# Microcontroller.net
KiCad netlist of a schematic drawn in Altium Designer
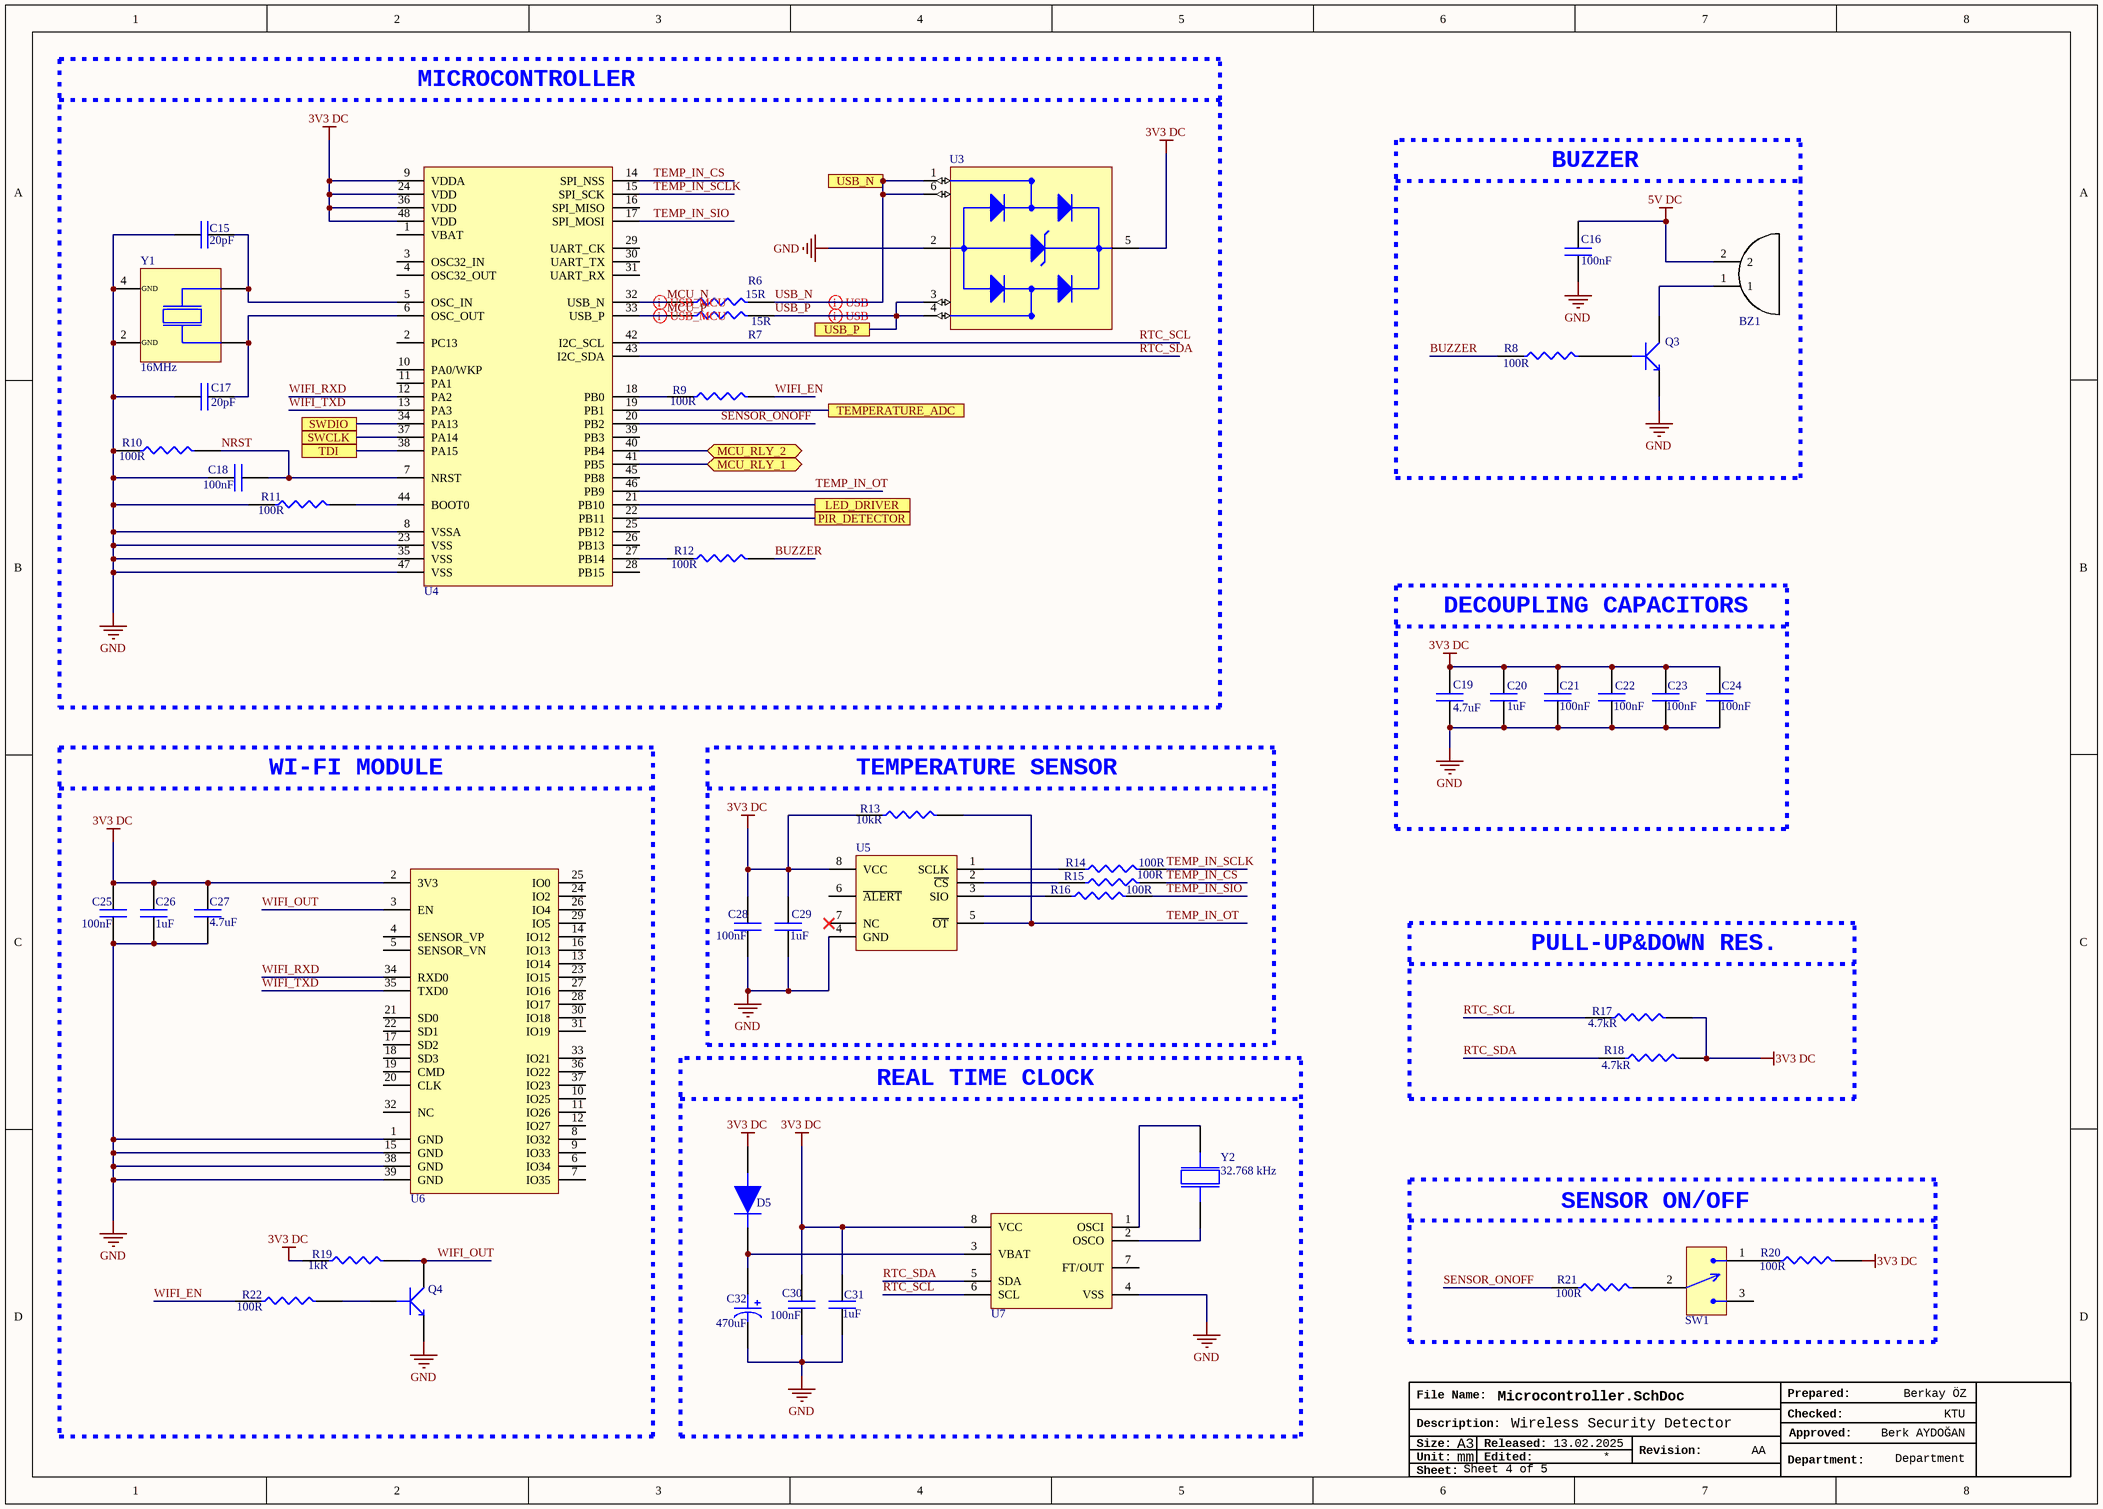
[diagram p0: Microcontroller.SchDoc]

(export (version "E")
  (design (tool "Eeschema 10.0.6"))
  (components
    (comp (ref "BZ1")
      (value "CMI-9605IC-0580T")
      (footprint "CMI-9605IC")
      (description "Buzzers Indicator, Internally Driven Magnetic 5 V 30mA 2.7kHz 80dB @ 5V, 10cm Through Hole PC Pins")
      (fields (field (name "MANUFACTURER") "CUI Devices") (field (name "DESIGNED BY") "berkay"))
      (libsource (lib "FirstProject_Library") (part "CMI-9605IC-0580T"))
    )
    (comp (ref "C15")
      (value "CL10C200JB8NNNC")
      (footprint "CAP_0603")
      (description "Ceramic Capacitor, 20pF, 50 V, 5%, Pad SMD 0603 [1608 Metric]")
      (fields
        (field (name "MANUFACTURER") "Samsung")
        (field (name "CAPACITANCE") "20pF")
        (field (name "DESIGNED BY") "berkay")
      )
      (libsource (lib "FirstProject_Library") (part "CAP CER 20pF 0603"))
    )
    (comp (ref "C16")
      (value "CL21B104KBCNNNC")
      (footprint "CAP_0805")
      (description "Ceramic Capacitor, 0.1 uF, 50 V, ï¿½ 10%, X7R, 0805 [2012 Metric]")
      (fields
        (field (name "MANUFACTURER") "Samsung")
        (field (name "TOLERANCE") "10%")
        (field (name "CAPACITANCE") "100nF")
        (field (name "DESIGNED BY") "berkay")
      )
      (libsource (lib "FirstProject_Library") (part "CAP CER 100nF 0805"))
    )
    (comp (ref "C17")
      (value "CL10C200JB8NNNC")
      (footprint "CAP_0603")
      (description "Ceramic Capacitor, 20pF, 50 V, 5%, Pad SMD 0603 [1608 Metric]")
      (fields
        (field (name "MANUFACTURER") "Samsung")
        (field (name "CAPACITANCE") "20pF")
        (field (name "DESIGNED BY") "berkay")
      )
      (libsource (lib "FirstProject_Library") (part "CAP CER 20pF 0603"))
    )
    (comp (ref "C18")
      (value "CL21B104KBCNNNC")
      (footprint "CAP_0805")
      (description "Ceramic Capacitor, 0.1 uF, 50 V, ï¿½ 10%, X7R, 0805 [2012 Metric]")
      (fields
        (field (name "MANUFACTURER") "Samsung")
        (field (name "TOLERANCE") "10%")
        (field (name "CAPACITANCE") "100nF")
        (field (name "DESIGNED BY") "berkay")
      )
      (libsource (lib "FirstProject_Library") (part "CAP CER 100nF 0805"))
    )
    (comp (ref "C19")
      (value "CL21A475KAQNNNE")
      (footprint "CAP_0805")
      (description "Ceramic Capacitor, 4.7 uF, 25 V, ± 10%, X5R, 0805 [2012 Metric]")
      (fields
        (field (name "MANUFACTURER") "Samsung")
        (field (name "TOLERANCE") "10%")
        (field (name "CAPACITANCE") "4.7uF")
        (field (name "DESIGNED BY") "berkay")
      )
      (libsource (lib "FirstProject_Library") (part "CAP CER 4.7uF 0805"))
    )
    (comp (ref "C20")
      (value "CL21B105KBFNNNE")
      (footprint "CAP_0805")
      (description "Ceramic Capacitor, 1 uF, 50 V, ï¿½ 10%, X7R, 0805 [2012 Metric]")
      (fields
        (field (name "MANUFACTURER") "Samsung")
        (field (name "TOLERANCE") "10%")
        (field (name "CAPACITANCE") "1uF")
        (field (name "DESIGNED BY") "berkay")
      )
      (libsource (lib "FirstProject_Library") (part "CAP CER 1uF 0805"))
    )
    (comp (ref "C21")
      (value "CL21B104KBCNNNC")
      (footprint "CAP_0805")
      (description "Ceramic Capacitor, 0.1 uF, 50 V, ï¿½ 10%, X7R, 0805 [2012 Metric]")
      (fields
        (field (name "MANUFACTURER") "Samsung")
        (field (name "TOLERANCE") "10%")
        (field (name "CAPACITANCE") "100nF")
        (field (name "DESIGNED BY") "berkay")
      )
      (libsource (lib "FirstProject_Library") (part "CAP CER 100nF 0805"))
    )
    (comp (ref "C22")
      (value "CL21B104KBCNNNC")
      (footprint "CAP_0805")
      (description "Ceramic Capacitor, 0.1 uF, 50 V, ï¿½ 10%, X7R, 0805 [2012 Metric]")
      (fields
        (field (name "MANUFACTURER") "Samsung")
        (field (name "TOLERANCE") "10%")
        (field (name "CAPACITANCE") "100nF")
        (field (name "DESIGNED BY") "berkay")
      )
      (libsource (lib "FirstProject_Library") (part "CAP CER 100nF 0805"))
    )
    (comp (ref "C23")
      (value "CL21B104KBCNNNC")
      (footprint "CAP_0805")
      (description "Ceramic Capacitor, 0.1 uF, 50 V, ï¿½ 10%, X7R, 0805 [2012 Metric]")
      (fields
        (field (name "MANUFACTURER") "Samsung")
        (field (name "TOLERANCE") "10%")
        (field (name "CAPACITANCE") "100nF")
        (field (name "DESIGNED BY") "berkay")
      )
      (libsource (lib "FirstProject_Library") (part "CAP CER 100nF 0805"))
    )
    (comp (ref "C24")
      (value "CL21B104KBCNNNC")
      (footprint "CAP_0805")
      (description "Ceramic Capacitor, 0.1 uF, 50 V, ï¿½ 10%, X7R, 0805 [2012 Metric]")
      (fields
        (field (name "MANUFACTURER") "Samsung")
        (field (name "TOLERANCE") "10%")
        (field (name "CAPACITANCE") "100nF")
        (field (name "DESIGNED BY") "berkay")
      )
      (libsource (lib "FirstProject_Library") (part "CAP CER 100nF 0805"))
    )
    (comp (ref "C25")
      (value "C0603C104K4RACTU")
      (footprint "CAP_0603")
      (description "Ceramic Capacitor, 0.1 uF, 16 V, ï¿½ 10%, X7R, 0603 [1608 Metric]")
      (fields
        (field (name "MANUFACTURER") "KEMET")
        (field (name "TOLERANCE") "10%")
        (field (name "CAPACITANCE") "100nF")
        (field (name "DESIGNED BY") "berkay")
      )
      (libsource (lib "FirstProject_Library") (part "CAP CER 100nF 0603"))
    )
    (comp (ref "C26")
      (value "CL21B105KBFNNNE")
      (footprint "CAP_0805")
      (description "Ceramic Capacitor, 1 uF, 50 V, ï¿½ 10%, X7R, 0805 [2012 Metric]")
      (fields
        (field (name "MANUFACTURER") "Samsung")
        (field (name "TOLERANCE") "10%")
        (field (name "CAPACITANCE") "1uF")
        (field (name "DESIGNED BY") "berkay")
      )
      (libsource (lib "FirstProject_Library") (part "CAP CER 1uF 0805"))
    )
    (comp (ref "C27")
      (value "CL21A475KAQNNNE")
      (footprint "CAP_0805")
      (description "Ceramic Capacitor, 4.7 uF, 25 V, ± 10%, X5R, 0805 [2012 Metric]")
      (fields
        (field (name "MANUFACTURER") "Samsung")
        (field (name "TOLERANCE") "10%")
        (field (name "CAPACITANCE") "4.7uF")
        (field (name "DESIGNED BY") "berkay")
      )
      (libsource (lib "FirstProject_Library") (part "CAP CER 4.7uF 0805"))
    )
    (comp (ref "C28")
      (value "C0603C104K4RACTU")
      (footprint "CAP_0603")
      (description "Ceramic Capacitor, 0.1 uF, 16 V, ï¿½ 10%, X7R, 0603 [1608 Metric]")
      (fields
        (field (name "MANUFACTURER") "KEMET")
        (field (name "TOLERANCE") "10%")
        (field (name "CAPACITANCE") "100nF")
        (field (name "DESIGNED BY") "berkay")
      )
      (libsource (lib "FirstProject_Library") (part "CAP CER 100nF 0603"))
    )
    (comp (ref "C29")
      (value "CL21B105KBFNNNE")
      (footprint "CAP_0805")
      (description "Ceramic Capacitor, 1 uF, 50 V, ï¿½ 10%, X7R, 0805 [2012 Metric]")
      (fields
        (field (name "MANUFACTURER") "Samsung")
        (field (name "TOLERANCE") "10%")
        (field (name "CAPACITANCE") "1uF")
        (field (name "DESIGNED BY") "berkay")
      )
      (libsource (lib "FirstProject_Library") (part "CAP CER 1uF 0805"))
    )
    (comp (ref "C30")
      (value "CL21B104KBCNNNC")
      (footprint "CAP_0805")
      (description "Ceramic Capacitor, 0.1 uF, 50 V, ï¿½ 10%, X7R, 0805 [2012 Metric]")
      (fields
        (field (name "MANUFACTURER") "Samsung")
        (field (name "TOLERANCE") "10%")
        (field (name "CAPACITANCE") "100nF")
        (field (name "DESIGNED BY") "berkay")
      )
      (libsource (lib "FirstProject_Library") (part "CAP CER 100nF 0805"))
    )
    (comp (ref "C31")
      (value "CL21B105KBFNNNE")
      (footprint "CAP_0805")
      (description "Ceramic Capacitor, 1 uF, 50 V, ï¿½ 10%, X7R, 0805 [2012 Metric]")
      (fields
        (field (name "MANUFACTURER") "Samsung")
        (field (name "TOLERANCE") "10%")
        (field (name "CAPACITANCE") "1uF")
        (field (name "DESIGNED BY") "berkay")
      )
      (libsource (lib "FirstProject_Library") (part "CAP CER 1uF 0805"))
    )
    (comp (ref "C32")
      (value "ESH477M050AH4AA")
      (footprint "CAP_RADIAL_D10_P5")
      (description "Electrolytic capacitor, 470 µF, 50 V (DC), ±20 %, radial, pitch 5 mm, Ø 13 mm")
      (fields
        (field (name "MANUFACTURER") "KEMET")
        (field (name "CAPACITANCE") "470uF")
        (field (name "DESIGNED BY") "berkay")
      )
      (libsource (lib "FirstProject_Library") (part "CAP ALU ELEC 470uF 50V"))
    )
    (comp (ref "D5")
      (value "1N4148WS")
      (footprint "SOD323F")
      (description "Diode Ultra Fast Recovery Rectifier 75V 0.15A 2-Pin SOD-323F T/R")
      (fields
        (field (name "MANUFACTURER") "ON Semiconductor / Fairchild")
        (field (name "DESIGNED BY") "berkay")
      )
      (libsource (lib "FirstProject_Library") (part "1N4148WS"))
    )
    (comp (ref "Q3")
      (value "MMBT3904-7-F")
      (footprint "SOT23F")
      (description "Transistor General Purpose BJT NPN 40 Volt 0.2A Automotive 3-Pin SOT-23")
      (fields (field (name "MANUFACTURER") "Diodes Zetex") (field (name "DESIGNED BY") "berkay"))
      (libsource (lib "FirstProject_Library") (part "MMBT3904-7-F"))
    )
    (comp (ref "Q4")
      (value "MMBT3904-7-F")
      (footprint "SOT23F")
      (description "Transistor General Purpose BJT NPN 40 Volt 0.2A Automotive 3-Pin SOT-23")
      (fields (field (name "MANUFACTURER") "Diodes Zetex") (field (name "DESIGNED BY") "berkay"))
      (libsource (lib "FirstProject_Library") (part "MMBT3904-7-F"))
    )
    (comp (ref "R6")
      (value "RC0603JR-0715RL")
      (footprint "RES_0603")
      (description "SMD Chip Resistor, 15 Ohm, ï¿½ 5%, 100 mW, 0603 [1608 Metric], Thick Film, General Purpose")
      (fields
        (field (name "MANUFACTURER") "Yageo")
        (field (name "RESISTANCE") "15R")
        (field (name "DESIGNED BY") "berkay")
      )
      (libsource (lib "FirstProject_Library") (part "RES 15 OHM 0603"))
    )
    (comp (ref "R7")
      (value "RC0603JR-0715RL")
      (footprint "RES_0603")
      (description "SMD Chip Resistor, 15 Ohm, ï¿½ 5%, 100 mW, 0603 [1608 Metric], Thick Film, General Purpose")
      (fields
        (field (name "MANUFACTURER") "Yageo")
        (field (name "RESISTANCE") "15R")
        (field (name "DESIGNED BY") "berkay")
      )
      (libsource (lib "FirstProject_Library") (part "RES 15 OHM 0603"))
    )
    (comp (ref "R8")
      (value "RC0603FR-07100RL")
      (footprint "RES_0603")
      (description "SMD Chip Resistor, 100 Ohm, ï¿½ 1%, 100 mW, 0603 [1608 Metric], Thick Film, General Purpose")
      (fields
        (field (name "MANUFACTURER") "Yageo")
        (field (name "TOLERANCE") "1%")
        (field (name "RESISTANCE") "100R")
        (field (name "DESIGNED BY") "berkay")
      )
      (libsource (lib "FirstProject_Library") (part "RES 100 OHM 0603"))
    )
    (comp (ref "R9")
      (value "RC0603FR-07100RL")
      (footprint "RES_0603")
      (description "SMD Chip Resistor, 100 Ohm, ï¿½ 1%, 100 mW, 0603 [1608 Metric], Thick Film, General Purpose")
      (fields
        (field (name "MANUFACTURER") "Yageo")
        (field (name "TOLERANCE") "1%")
        (field (name "RESISTANCE") "100R")
        (field (name "DESIGNED BY") "berkay")
      )
      (libsource (lib "FirstProject_Library") (part "RES 100 OHM 0603"))
    )
    (comp (ref "R10")
      (value "RC0603FR-07100RL")
      (footprint "RES_0603")
      (description "SMD Chip Resistor, 100 Ohm, ï¿½ 1%, 100 mW, 0603 [1608 Metric], Thick Film, General Purpose")
      (fields
        (field (name "MANUFACTURER") "Yageo")
        (field (name "TOLERANCE") "1%")
        (field (name "RESISTANCE") "100R")
        (field (name "DESIGNED BY") "berkay")
      )
      (libsource (lib "FirstProject_Library") (part "RES 100 OHM 0603"))
    )
    (comp (ref "R11")
      (value "RC0603FR-07100RL")
      (footprint "RES_0603")
      (description "SMD Chip Resistor, 100 Ohm, ï¿½ 1%, 100 mW, 0603 [1608 Metric], Thick Film, General Purpose")
      (fields
        (field (name "MANUFACTURER") "Yageo")
        (field (name "TOLERANCE") "1%")
        (field (name "RESISTANCE") "100R")
        (field (name "DESIGNED BY") "berkay")
      )
      (libsource (lib "FirstProject_Library") (part "RES 100 OHM 0603"))
    )
    (comp (ref "R12")
      (value "RC0603FR-07100RL")
      (footprint "RES_0603")
      (description "SMD Chip Resistor, 100 Ohm, ï¿½ 1%, 100 mW, 0603 [1608 Metric], Thick Film, General Purpose")
      (fields
        (field (name "MANUFACTURER") "Yageo")
        (field (name "TOLERANCE") "1%")
        (field (name "RESISTANCE") "100R")
        (field (name "DESIGNED BY") "berkay")
      )
      (libsource (lib "FirstProject_Library") (part "RES 100 OHM 0603"))
    )
    (comp (ref "R13")
      (value "RC0603FR-0710KL")
      (footprint "RES_0603")
      (description "SMD Chip Resistor, 10 kOhm, ï¿½ 1%, 100 mW, 0603 [1608 Metric], Thick Film, General Purpose")
      (fields
        (field (name "MANUFACTURER") "Yageo")
        (field (name "TOLERANCE") "1%")
        (field (name "RESISTANCE") "10kR")
        (field (name "DESIGNED BY") "berkay")
      )
      (libsource (lib "FirstProject_Library") (part "RES 10K OHM 0603"))
    )
    (comp (ref "R14")
      (value "RC0603FR-07100RL")
      (footprint "RES_0603")
      (description "SMD Chip Resistor, 100 Ohm, ï¿½ 1%, 100 mW, 0603 [1608 Metric], Thick Film, General Purpose")
      (fields
        (field (name "MANUFACTURER") "Yageo")
        (field (name "TOLERANCE") "1%")
        (field (name "RESISTANCE") "100R")
        (field (name "DESIGNED BY") "berkay")
      )
      (libsource (lib "FirstProject_Library") (part "RES 100 OHM 0603"))
    )
    (comp (ref "R15")
      (value "RC0603FR-07100RL")
      (footprint "RES_0603")
      (description "SMD Chip Resistor, 100 Ohm, ï¿½ 1%, 100 mW, 0603 [1608 Metric], Thick Film, General Purpose")
      (fields
        (field (name "MANUFACTURER") "Yageo")
        (field (name "TOLERANCE") "1%")
        (field (name "RESISTANCE") "100R")
        (field (name "DESIGNED BY") "berkay")
      )
      (libsource (lib "FirstProject_Library") (part "RES 100 OHM 0603"))
    )
    (comp (ref "R16")
      (value "RC0603FR-07100RL")
      (footprint "RES_0603")
      (description "SMD Chip Resistor, 100 Ohm, ï¿½ 1%, 100 mW, 0603 [1608 Metric], Thick Film, General Purpose")
      (fields
        (field (name "MANUFACTURER") "Yageo")
        (field (name "TOLERANCE") "1%")
        (field (name "RESISTANCE") "100R")
        (field (name "DESIGNED BY") "berkay")
      )
      (libsource (lib "FirstProject_Library") (part "RES 100 OHM 0603"))
    )
    (comp (ref "R17")
      (value "RC0603FR-074K7L")
      (footprint "RES_0603")
      (description "SMD Chip Resistor, 4.7 kOhm, ï¿½ 1%, 100 mW, 0603 [1608 Metric], Thick Film, General Purpose")
      (fields
        (field (name "MANUFACTURER") "Yageo")
        (field (name "TOLERANCE") "1%")
        (field (name "RESISTANCE") "4.7kR")
        (field (name "DESIGNED BY") "berkay")
      )
      (libsource (lib "FirstProject_Library") (part "RES 4K7 OHM 0603"))
    )
    (comp (ref "R18")
      (value "RC0603FR-074K7L")
      (footprint "RES_0603")
      (description "SMD Chip Resistor, 4.7 kOhm, ï¿½ 1%, 100 mW, 0603 [1608 Metric], Thick Film, General Purpose")
      (fields
        (field (name "MANUFACTURER") "Yageo")
        (field (name "TOLERANCE") "1%")
        (field (name "RESISTANCE") "4.7kR")
        (field (name "DESIGNED BY") "berkay")
      )
      (libsource (lib "FirstProject_Library") (part "RES 4K7 OHM 0603"))
    )
    (comp (ref "R19")
      (value "RC0603FR-071KL")
      (footprint "RES_0603")
      (description "SMD Chip Resistor, 1 kOhm, ï¿½ 1%, 100 mW, 0603 [1608 Metric], Thick Film, General Purpose")
      (fields
        (field (name "MANUFACTURER") "Yageo")
        (field (name "TOLERANCE") "1%")
        (field (name "RESISTANCE") "1kR")
        (field (name "DESIGNED BY") "berkay")
      )
      (libsource (lib "FirstProject_Library") (part "RES 1K OHM 0603"))
    )
    (comp (ref "R20")
      (value "RC0603FR-07100RL")
      (footprint "RES_0603")
      (description "SMD Chip Resistor, 100 Ohm, ï¿½ 1%, 100 mW, 0603 [1608 Metric], Thick Film, General Purpose")
      (fields
        (field (name "MANUFACTURER") "Yageo")
        (field (name "TOLERANCE") "1%")
        (field (name "RESISTANCE") "100R")
        (field (name "DESIGNED BY") "berkay")
      )
      (libsource (lib "FirstProject_Library") (part "RES 100 OHM 0603"))
    )
    (comp (ref "R21")
      (value "RC0603FR-07100RL")
      (footprint "RES_0603")
      (description "SMD Chip Resistor, 100 Ohm, ï¿½ 1%, 100 mW, 0603 [1608 Metric], Thick Film, General Purpose")
      (fields
        (field (name "MANUFACTURER") "Yageo")
        (field (name "TOLERANCE") "1%")
        (field (name "RESISTANCE") "100R")
        (field (name "DESIGNED BY") "berkay")
      )
      (libsource (lib "FirstProject_Library") (part "RES 100 OHM 0603"))
    )
    (comp (ref "R22")
      (value "RC0603FR-07100RL")
      (footprint "RES_0603")
      (description "SMD Chip Resistor, 100 Ohm, ï¿½ 1%, 100 mW, 0603 [1608 Metric], Thick Film, General Purpose")
      (fields
        (field (name "MANUFACTURER") "Yageo")
        (field (name "TOLERANCE") "1%")
        (field (name "RESISTANCE") "100R")
        (field (name "DESIGNED BY") "berkay")
      )
      (libsource (lib "FirstProject_Library") (part "RES 100 OHM 0603"))
    )
    (comp (ref "SW1")
      (value "EG1215AA")
      (footprint "EG1215AA")
      (description "Slide Switch, SPDT, ON-ON, 25 mA, 24V DC, Surf. Mt., RA, Gull Wing ¦ E-Switch EG1215AA")
      (fields (field (name "MANUFACTURER") "E-Switch") (field (name "DESIGNED BY") "berkay"))
      (libsource (lib "FirstProject_Library") (part "EG1215AA"))
    )
    (comp (ref "U3")
      (value "USBLC6-2SC6")
      (footprint "SOT23-6L")
      (description "ESD Suppressor Diode Array Dual Uni-Dir 15kV Air Gap/15kV Contact Disc 6-Pin SOT-23 T/R")
      (fields (field (name "MANUFACTURER") "STMicroelectronics") (field (name "DESIGNED BY") "berkay"))
      (libsource (lib "FirstProject_Library") (part "USB PROTECTION"))
    )
    (comp (ref "U4")
      (value "STM32F103C6T6A")
      (footprint "LQFP-48")
      (description "MCU 32-bit STM32F ARM Cortex M3 RISC 32KB Flash 2.5V/3.3V 48-Pin LQFP Tray")
      (fields (field (name "MANUFACTURER") "STMicroelectronics") (field (name "DESIGNED BY") "Berkay"))
      (libsource (lib "FirstProject_Library") (part "STM32F103C6T6A"))
    )
    (comp (ref "U5")
      (value "MAX6662")
      (footprint "SOIC 8")
      (description "Temp Sensor Digital Serial (3-Wire, SPI) 8-Pin SOIC N Tube")
      (fields
        (field (name "MANUFACTURER") "Maxim")
        (field (name "MANUFACTURER PART NUMBER") "MAX6662MSA+")
        (field (name "DESIGNED BY") "berkay")
      )
      (libsource (lib "FirstProject_Library") (part "MAX6662MSA+"))
    )
    (comp (ref "U6")
      (value "ESP32-WROOM-32")
      (footprint "ESP32-32")
      (description "SMD MODULE, ESP32-D0WDQ6, 32MBIT")
      (fields (field (name "MANUFACTURER") "Espressif Systems") (field (name "DESIGNED BY") "berkay"))
      (libsource (lib "FirstProject_Library") (part "ESP32-WROOM-32"))
    )
    (comp (ref "U7")
      (value "M41T00SM6F")
      (footprint "SOIC 8")
      (description "M41T00S Series 5.5 V I2C / 2-Wire / Serial SMT Real Time Clock - SOIC-8")
      (fields (field (name "MANUFACTURER") "STMicroelectronics") (field (name "DESIGNED BY") "berkay"))
      (libsource (lib "FirstProject_Library") (part "M41T00SM6F"))
    )
    (comp (ref "Y1")
      (value "ECS-160-20-30B-TR")
      (footprint "ECS")
      (description "Crystal 16MHz ±30ppm (Tol) ±50ppm (Stability) 20pF FUND 50Ohm 4-Pin Mini-SMD T/R")
      (fields
        (field (name "MANUFACTURER") "ECS International")
        (field (name "FREQUENCY") "16MHz")
        (field (name "DESIGNED BY") "berkay")
      )
      (libsource (lib "FirstProject_Library") (part "CRYSTAL 16MHz"))
    )
    (comp (ref "Y2")
      (value "ABS05-32.768KHZ-T")
      (footprint "ABS05")
      (description "Crystal 0.032768MHz ±20ppm (Tol) 12.5pF Flexural 90000Ohm 2-Pin CSMD T/R")
      (fields
        (field (name "MANUFACTURER") "Abracon")
        (field (name "TOLERANCE") "20ppm")
        (field (name "OPERATING FREQUENCY") "32.768 kHz")
        (field (name "DESIGNED BY") "berkay")
      )
      (libsource (lib "FirstProject_Library") (part "CRYSTAL 32.768kHz"))
    )
  )
  (nets
    (net (code "1") (name "/BUZZER") (class "Default")
      (node (ref "R12") (pin "2") (pinfunction "2_2") (pintype "passive"))
      (node (ref "R8") (pin "1") (pinfunction "1_1") (pintype "passive"))
    )
    (net (code "2") (name "/LED_DRIVER") (class "Default")
      (node (ref "U4") (pin "21") (pinfunction "PB10_21") (pintype "passive"))
    )
    (net (code "3") (name "/MCU_N") (class "Default")
      (node (ref "R6") (pin "1") (pinfunction "1_1") (pintype "passive"))
      (node (ref "U4") (pin "32") (pinfunction "USB_N_32") (pintype "passive"))
    )
    (net (code "4") (name "/MCU_P") (class "Default")
      (node (ref "R7") (pin "1") (pinfunction "1_1") (pintype "passive"))
      (node (ref "U4") (pin "33") (pinfunction "USB_P_33") (pintype "passive"))
    )
    (net (code "5") (name "/MCU_RLY_1") (class "Default")
      (node (ref "U4") (pin "41") (pinfunction "PB5_41") (pintype "passive"))
    )
    (net (code "6") (name "/MCU_RLY_2") (class "Default")
      (node (ref "U4") (pin "40") (pinfunction "PB4_40") (pintype "passive"))
    )
    (net (code "7") (name "/NRST") (class "Default")
      (node (ref "C18") (pin "1") (pinfunction "1_1") (pintype "passive"))
      (node (ref "R10") (pin "2") (pinfunction "2_2") (pintype "passive"))
      (node (ref "U4") (pin "7") (pinfunction "NRST_7") (pintype "passive"))
    )
    (net (code "8") (name "/PIR_DETECTOR") (class "Default")
      (node (ref "U4") (pin "22") (pinfunction "PB11_22") (pintype "passive"))
    )
    (net (code "9") (name "/RTC_SCL") (class "Default")
      (node (ref "R17") (pin "1") (pinfunction "1_1") (pintype "passive"))
      (node (ref "U4") (pin "42") (pinfunction "I2C_SCL_42") (pintype "passive"))
      (node (ref "U7") (pin "6") (pinfunction "SCL_6") (pintype "passive"))
    )
    (net (code "10") (name "/RTC_SDA") (class "Default")
      (node (ref "R18") (pin "1") (pinfunction "1_1") (pintype "passive"))
      (node (ref "U4") (pin "43") (pinfunction "I2C_SDA_43") (pintype "passive"))
      (node (ref "U7") (pin "5") (pinfunction "SDA_5") (pintype "passive"))
    )
    (net (code "11") (name "/SENSOR_ONOFF") (class "Default")
      (node (ref "R21") (pin "1") (pinfunction "1_1") (pintype "passive"))
      (node (ref "U4") (pin "20") (pinfunction "PB2_20") (pintype "passive"))
    )
    (net (code "12") (name "/SWCLK") (class "Default")
      (node (ref "U4") (pin "37") (pinfunction "PA14_37") (pintype "passive"))
    )
    (net (code "13") (name "/SWDIO") (class "Default")
      (node (ref "U4") (pin "34") (pinfunction "PA13_34") (pintype "passive"))
    )
    (net (code "14") (name "/TDI") (class "Default")
      (node (ref "U4") (pin "38") (pinfunction "PA15_38") (pintype "passive"))
    )
    (net (code "15") (name "/TEMPERATURE_ADC") (class "Default")
      (node (ref "U4") (pin "19") (pinfunction "PB1_19") (pintype "passive"))
    )
    (net (code "16") (name "/TEMP_IN_CS") (class "Default")
      (node (ref "R15") (pin "2") (pinfunction "2_2") (pintype "passive"))
      (node (ref "U4") (pin "14") (pinfunction "SPI_NSS_14") (pintype "passive"))
    )
    (net (code "17") (name "/TEMP_IN_OT") (class "Default")
      (node (ref "R13") (pin "2") (pinfunction "2_2") (pintype "passive"))
      (node (ref "U4") (pin "46") (pinfunction "PB9_46") (pintype "passive"))
      (node (ref "U5") (pin "5") (pinfunction "~{OT}_5") (pintype "passive"))
    )
    (net (code "18") (name "/TEMP_IN_SCLK") (class "Default")
      (node (ref "R14") (pin "2") (pinfunction "2_2") (pintype "passive"))
      (node (ref "U4") (pin "15") (pinfunction "SPI_SCK_15") (pintype "passive"))
    )
    (net (code "19") (name "/TEMP_IN_SIO") (class "Default")
      (node (ref "R16") (pin "2") (pinfunction "2_2") (pintype "passive"))
      (node (ref "U4") (pin "17") (pinfunction "SPI_MOSI_17") (pintype "passive"))
    )
    (net (code "20") (name "/USB_N") (class "Default")
      (node (ref "R6") (pin "2") (pinfunction "2_2") (pintype "passive"))
      (node (ref "U3") (pin "1") (pinfunction "I/O1_IN_1") (pintype "bidirectional"))
      (node (ref "U3") (pin "6") (pinfunction "I/O1_OUT_6") (pintype "bidirectional"))
    )
    (net (code "21") (name "/USB_P") (class "Default")
      (node (ref "R7") (pin "2") (pinfunction "2_2") (pintype "passive"))
      (node (ref "U3") (pin "3") (pinfunction "I/O2_IN_3") (pintype "bidirectional"))
      (node (ref "U3") (pin "4") (pinfunction "I/O2_OUT_4") (pintype "bidirectional"))
    )
    (net (code "22") (name "/WIFI_EN") (class "Default")
      (node (ref "R22") (pin "1") (pinfunction "1_1") (pintype "passive"))
      (node (ref "R9") (pin "2") (pinfunction "2_2") (pintype "passive"))
    )
    (net (code "23") (name "/WIFI_OUT") (class "Default")
      (node (ref "Q4") (pin "3") (pinfunction "C_3") (pintype "passive"))
      (node (ref "R19") (pin "2") (pinfunction "2_2") (pintype "passive"))
      (node (ref "U6") (pin "3") (pinfunction "EN_3") (pintype "passive"))
    )
    (net (code "24") (name "/WIFI_RXD") (class "Default")
      (node (ref "U4") (pin "12") (pinfunction "PA2_12") (pintype "passive"))
      (node (ref "U6") (pin "34") (pinfunction "RXD0_34") (pintype "passive"))
    )
    (net (code "25") (name "/WIFI_TXD") (class "Default")
      (node (ref "U4") (pin "13") (pinfunction "PA3_13") (pintype "passive"))
      (node (ref "U6") (pin "35") (pinfunction "TXD0_35") (pintype "passive"))
    )
    (net (code "26") (name "3V3 DC") (class "Default")
      (node (ref "C19") (pin "2") (pinfunction "2_2") (pintype "passive"))
      (node (ref "C20") (pin "2") (pinfunction "2_2") (pintype "passive"))
      (node (ref "C21") (pin "2") (pinfunction "2_2") (pintype "passive"))
      (node (ref "C22") (pin "2") (pinfunction "2_2") (pintype "passive"))
      (node (ref "C23") (pin "2") (pinfunction "2_2") (pintype "passive"))
      (node (ref "C24") (pin "2") (pinfunction "2_2") (pintype "passive"))
      (node (ref "C25") (pin "2") (pinfunction "2_2") (pintype "passive"))
      (node (ref "C26") (pin "2") (pinfunction "2_2") (pintype "passive"))
      (node (ref "C27") (pin "2") (pinfunction "2_2") (pintype "passive"))
      (node (ref "C28") (pin "2") (pinfunction "2_2") (pintype "passive"))
      (node (ref "C29") (pin "2") (pinfunction "2_2") (pintype "passive"))
      (node (ref "C30") (pin "2") (pinfunction "2_2") (pintype "passive"))
      (node (ref "C31") (pin "2") (pinfunction "2_2") (pintype "passive"))
      (node (ref "D5") (pin "A") (pinfunction "A_A") (pintype "passive"))
      (node (ref "R13") (pin "1") (pinfunction "1_1") (pintype "passive"))
      (node (ref "R17") (pin "2") (pinfunction "2_2") (pintype "passive"))
      (node (ref "R18") (pin "2") (pinfunction "2_2") (pintype "passive"))
      (node (ref "R19") (pin "1") (pinfunction "1_1") (pintype "passive"))
      (node (ref "R20") (pin "2") (pinfunction "2_2") (pintype "passive"))
      (node (ref "U3") (pin "5") (pinfunction "VBUS_5") (pintype "power_in"))
      (node (ref "U4") (pin "24") (pinfunction "VDD_24") (pintype "passive"))
      (node (ref "U4") (pin "36") (pinfunction "VDD_36") (pintype "passive"))
      (node (ref "U4") (pin "48") (pinfunction "VDD_48") (pintype "passive"))
      (node (ref "U4") (pin "9") (pinfunction "VDDA_9") (pintype "passive"))
      (node (ref "U5") (pin "8") (pinfunction "VCC_8") (pintype "passive"))
      (node (ref "U6") (pin "2") (pinfunction "3V3_2") (pintype "passive"))
      (node (ref "U7") (pin "8") (pinfunction "VCC_8") (pintype "passive"))
    )
    (net (code "27") (name "5V DC") (class "Default")
      (node (ref "BZ1") (pin "2") (pinfunction "2_2") (pintype "passive"))
      (node (ref "C16") (pin "2") (pinfunction "2_2") (pintype "passive"))
    )
    (net (code "28") (name "GND") (class "Default")
      (node (ref "C15") (pin "1") (pinfunction "1_1") (pintype "passive"))
      (node (ref "C16") (pin "1") (pinfunction "1_1") (pintype "passive"))
      (node (ref "C17") (pin "1") (pinfunction "1_1") (pintype "passive"))
      (node (ref "C18") (pin "2") (pinfunction "2_2") (pintype "passive"))
      (node (ref "C19") (pin "1") (pinfunction "1_1") (pintype "passive"))
      (node (ref "C20") (pin "1") (pinfunction "1_1") (pintype "passive"))
      (node (ref "C21") (pin "1") (pinfunction "1_1") (pintype "passive"))
      (node (ref "C22") (pin "1") (pinfunction "1_1") (pintype "passive"))
      (node (ref "C23") (pin "1") (pinfunction "1_1") (pintype "passive"))
      (node (ref "C24") (pin "1") (pinfunction "1_1") (pintype "passive"))
      (node (ref "C25") (pin "1") (pinfunction "1_1") (pintype "passive"))
      (node (ref "C26") (pin "1") (pinfunction "1_1") (pintype "passive"))
      (node (ref "C27") (pin "1") (pinfunction "1_1") (pintype "passive"))
      (node (ref "C28") (pin "1") (pinfunction "1_1") (pintype "passive"))
      (node (ref "C29") (pin "1") (pinfunction "1_1") (pintype "passive"))
      (node (ref "C30") (pin "1") (pinfunction "1_1") (pintype "passive"))
      (node (ref "C31") (pin "1") (pinfunction "1_1") (pintype "passive"))
      (node (ref "C32") (pin "2") (pinfunction "2_2") (pintype "passive"))
      (node (ref "Q3") (pin "2") (pinfunction "E_2") (pintype "passive"))
      (node (ref "Q4") (pin "2") (pinfunction "E_2") (pintype "passive"))
      (node (ref "R10") (pin "1") (pinfunction "1_1") (pintype "passive"))
      (node (ref "R11") (pin "1") (pinfunction "1_1") (pintype "passive"))
      (node (ref "U3") (pin "2") (pinfunction "GND_2") (pintype "power_in"))
      (node (ref "U4") (pin "23") (pinfunction "VSS_23") (pintype "passive"))
      (node (ref "U4") (pin "35") (pinfunction "VSS_35") (pintype "passive"))
      (node (ref "U4") (pin "47") (pinfunction "VSS_47") (pintype "passive"))
      (node (ref "U4") (pin "8") (pinfunction "VSSA_8") (pintype "passive"))
      (node (ref "U5") (pin "4") (pinfunction "GND_4") (pintype "passive"))
      (node (ref "U6") (pin "1") (pinfunction "GND_1") (pintype "passive"))
      (node (ref "U6") (pin "15") (pinfunction "GND_15") (pintype "passive"))
      (node (ref "U6") (pin "38") (pinfunction "GND_38") (pintype "passive"))
      (node (ref "U6") (pin "39") (pinfunction "GND_39") (pintype "passive"))
      (node (ref "U7") (pin "4") (pinfunction "VSS_4") (pintype "passive"))
      (node (ref "Y1") (pin "2") (pinfunction "GND_2") (pintype "passive"))
      (node (ref "Y1") (pin "4") (pinfunction "GND_4") (pintype "passive"))
    )
    (net (code "29") (name "Net-(Q3-B)") (class "Default")
      (node (ref "Q3") (pin "1") (pinfunction "B_1") (pintype "passive"))
      (node (ref "R8") (pin "2") (pinfunction "2_2") (pintype "passive"))
    )
    (net (code "30") (name "Net-(Q3-C)") (class "Default")
      (node (ref "BZ1") (pin "1") (pinfunction "1_1") (pintype "passive"))
      (node (ref "Q3") (pin "3") (pinfunction "C_3") (pintype "passive"))
    )
    (net (code "31") (name "Net-(Q4-B)") (class "Default")
      (node (ref "Q4") (pin "1") (pinfunction "B_1") (pintype "passive"))
      (node (ref "R22") (pin "2") (pinfunction "2_2") (pintype "passive"))
    )
    (net (code "32") (name "Net-(R20-Pad1)") (class "Default")
      (node (ref "R20") (pin "1") (pinfunction "1_1") (pintype "passive"))
      (node (ref "SW1") (pin "1") (pinfunction "1_1") (pintype "passive"))
    )
    (net (code "33") (name "Net-(R21-Pad2)") (class "Default")
      (node (ref "R21") (pin "2") (pinfunction "2_2") (pintype "passive"))
      (node (ref "SW1") (pin "2") (pinfunction "2_2") (pintype "passive"))
    )
    (net (code "34") (name "Net-(U4-BOOT0)") (class "Default")
      (node (ref "R11") (pin "2") (pinfunction "2_2") (pintype "passive"))
      (node (ref "U4") (pin "44") (pinfunction "BOOT0_44") (pintype "passive"))
    )
    (net (code "35") (name "Net-(U4-OSC_IN)") (class "Default")
      (node (ref "C15") (pin "2") (pinfunction "2_2") (pintype "passive"))
      (node (ref "U4") (pin "5") (pinfunction "OSC_IN_5") (pintype "passive"))
      (node (ref "Y1") (pin "3") (pinfunction "3_3") (pintype "passive"))
    )
    (net (code "36") (name "Net-(U4-OSC_OUT)") (class "Default")
      (node (ref "C17") (pin "2") (pinfunction "2_2") (pintype "passive"))
      (node (ref "U4") (pin "6") (pinfunction "OSC_OUT_6") (pintype "passive"))
      (node (ref "Y1") (pin "1") (pinfunction "1_1") (pintype "passive"))
    )
    (net (code "37") (name "Net-(U4-PB0)") (class "Default")
      (node (ref "R9") (pin "1") (pinfunction "1_1") (pintype "passive"))
      (node (ref "U4") (pin "18") (pinfunction "PB0_18") (pintype "passive"))
    )
    (net (code "38") (name "Net-(U4-PB14)") (class "Default")
      (node (ref "R12") (pin "1") (pinfunction "1_1") (pintype "passive"))
      (node (ref "U4") (pin "27") (pinfunction "PB14_27") (pintype "passive"))
    )
    (net (code "39") (name "Net-(U5-SCLK)") (class "Default")
      (node (ref "R14") (pin "1") (pinfunction "1_1") (pintype "passive"))
      (node (ref "U5") (pin "1") (pinfunction "SCLK_1") (pintype "passive"))
    )
    (net (code "40") (name "Net-(U5-SIO)") (class "Default")
      (node (ref "R16") (pin "1") (pinfunction "1_1") (pintype "passive"))
      (node (ref "U5") (pin "3") (pinfunction "SIO_3") (pintype "passive"))
    )
    (net (code "41") (name "Net-(U5-~{CS})") (class "Default")
      (node (ref "R15") (pin "1") (pinfunction "1_1") (pintype "passive"))
      (node (ref "U5") (pin "2") (pinfunction "~{CS}_2") (pintype "passive"))
    )
    (net (code "42") (name "Net-(U7-OSCI)") (class "Default")
      (node (ref "U7") (pin "1") (pinfunction "OSCI_1") (pintype "passive"))
      (node (ref "Y2") (pin "2") (pinfunction "2_2") (pintype "passive"))
    )
    (net (code "43") (name "Net-(U7-OSCO)") (class "Default")
      (node (ref "U7") (pin "2") (pinfunction "OSCO_2") (pintype "passive"))
      (node (ref "Y2") (pin "1") (pinfunction "1_1") (pintype "passive"))
    )
    (net (code "44") (name "Net-(U7-VBAT)") (class "Default")
      (node (ref "C32") (pin "1") (pinfunction "1_1") (pintype "passive"))
      (node (ref "D5") (pin "C") (pinfunction "C_C") (pintype "passive"))
      (node (ref "U7") (pin "3") (pinfunction "VBAT_3") (pintype "passive"))
    )
    (net (code "45") (name "unconnected-(SW1-Pad3)") (class "Default")
      (node (ref "SW1") (pin "3") (pinfunction "3_3") (pintype "passive"))
    )
    (net (code "46") (name "unconnected-(U4-OSC32_IN-Pad3)") (class "Default")
      (node (ref "U4") (pin "3") (pinfunction "OSC32_IN_3") (pintype "passive"))
    )
    (net (code "47") (name "unconnected-(U4-OSC32_OUT-Pad4)") (class "Default")
      (node (ref "U4") (pin "4") (pinfunction "OSC32_OUT_4") (pintype "passive"))
    )
    (net (code "48") (name "unconnected-(U4-PA0{slash}WKP-Pad10)") (class "Default")
      (node (ref "U4") (pin "10") (pinfunction "PA0/WKP_10") (pintype "passive"))
    )
    (net (code "49") (name "unconnected-(U4-PA1-Pad11)") (class "Default")
      (node (ref "U4") (pin "11") (pinfunction "PA1_11") (pintype "passive"))
    )
    (net (code "50") (name "unconnected-(U4-PB3-Pad39)") (class "Default")
      (node (ref "U4") (pin "39") (pinfunction "PB3_39") (pintype "passive"))
    )
    (net (code "51") (name "unconnected-(U4-PB8-Pad45)") (class "Default")
      (node (ref "U4") (pin "45") (pinfunction "PB8_45") (pintype "passive"))
    )
    (net (code "52") (name "unconnected-(U4-PB12-Pad25)") (class "Default")
      (node (ref "U4") (pin "25") (pinfunction "PB12_25") (pintype "passive"))
    )
    (net (code "53") (name "unconnected-(U4-PB13-Pad26)") (class "Default")
      (node (ref "U4") (pin "26") (pinfunction "PB13_26") (pintype "passive"))
    )
    (net (code "54") (name "unconnected-(U4-PB15-Pad28)") (class "Default")
      (node (ref "U4") (pin "28") (pinfunction "PB15_28") (pintype "passive"))
    )
    (net (code "55") (name "unconnected-(U4-PC13-Pad2)") (class "Default")
      (node (ref "U4") (pin "2") (pinfunction "PC13_2") (pintype "passive"))
    )
    (net (code "56") (name "unconnected-(U4-SPI_MISO-Pad16)") (class "Default")
      (node (ref "U4") (pin "16") (pinfunction "SPI_MISO_16") (pintype "passive"))
    )
    (net (code "57") (name "unconnected-(U4-UART_CK-Pad29)") (class "Default")
      (node (ref "U4") (pin "29") (pinfunction "UART_CK_29") (pintype "passive"))
    )
    (net (code "58") (name "unconnected-(U4-UART_RX-Pad31)") (class "Default")
      (node (ref "U4") (pin "31") (pinfunction "UART_RX_31") (pintype "passive"))
    )
    (net (code "59") (name "unconnected-(U4-UART_TX-Pad30)") (class "Default")
      (node (ref "U4") (pin "30") (pinfunction "UART_TX_30") (pintype "passive"))
    )
    (net (code "60") (name "unconnected-(U4-VBAT-Pad1)") (class "Default")
      (node (ref "U4") (pin "1") (pinfunction "VBAT_1") (pintype "passive"))
    )
    (net (code "61") (name "unconnected-(U5-NC-Pad7)") (class "Default")
      (node (ref "U5") (pin "7") (pinfunction "NC_7") (pintype "passive+no_connect"))
    )
    (net (code "62") (name "unconnected-(U5-~{ALERT}-Pad6)") (class "Default")
      (node (ref "U5") (pin "6") (pinfunction "~{ALERT}_6") (pintype "passive"))
    )
    (net (code "63") (name "unconnected-(U6-CLK-Pad20)") (class "Default")
      (node (ref "U6") (pin "20") (pinfunction "CLK_20") (pintype "passive"))
    )
    (net (code "64") (name "unconnected-(U6-CMD-Pad19)") (class "Default")
      (node (ref "U6") (pin "19") (pinfunction "CMD_19") (pintype "passive"))
    )
    (net (code "65") (name "unconnected-(U6-IO0-Pad25)") (class "Default")
      (node (ref "U6") (pin "25") (pinfunction "IO0_25") (pintype "passive"))
    )
    (net (code "66") (name "unconnected-(U6-IO2-Pad24)") (class "Default")
      (node (ref "U6") (pin "24") (pinfunction "IO2_24") (pintype "passive"))
    )
    (net (code "67") (name "unconnected-(U6-IO4-Pad26)") (class "Default")
      (node (ref "U6") (pin "26") (pinfunction "IO4_26") (pintype "passive"))
    )
    (net (code "68") (name "unconnected-(U6-IO5-Pad29)") (class "Default")
      (node (ref "U6") (pin "29") (pinfunction "IO5_29") (pintype "passive"))
    )
    (net (code "69") (name "unconnected-(U6-IO12-Pad14)") (class "Default")
      (node (ref "U6") (pin "14") (pinfunction "IO12_14") (pintype "passive"))
    )
    (net (code "70") (name "unconnected-(U6-IO13-Pad16)") (class "Default")
      (node (ref "U6") (pin "16") (pinfunction "IO13_16") (pintype "passive"))
    )
    (net (code "71") (name "unconnected-(U6-IO14-Pad13)") (class "Default")
      (node (ref "U6") (pin "13") (pinfunction "IO14_13") (pintype "passive"))
    )
    (net (code "72") (name "unconnected-(U6-IO15-Pad23)") (class "Default")
      (node (ref "U6") (pin "23") (pinfunction "IO15_23") (pintype "passive"))
    )
    (net (code "73") (name "unconnected-(U6-IO16-Pad27)") (class "Default")
      (node (ref "U6") (pin "27") (pinfunction "IO16_27") (pintype "passive"))
    )
    (net (code "74") (name "unconnected-(U6-IO17-Pad28)") (class "Default")
      (node (ref "U6") (pin "28") (pinfunction "IO17_28") (pintype "passive"))
    )
    (net (code "75") (name "unconnected-(U6-IO18-Pad30)") (class "Default")
      (node (ref "U6") (pin "30") (pinfunction "IO18_30") (pintype "passive"))
    )
    (net (code "76") (name "unconnected-(U6-IO19-Pad31)") (class "Default")
      (node (ref "U6") (pin "31") (pinfunction "IO19_31") (pintype "passive"))
    )
    (net (code "77") (name "unconnected-(U6-IO21-Pad33)") (class "Default")
      (node (ref "U6") (pin "33") (pinfunction "IO21_33") (pintype "passive"))
    )
    (net (code "78") (name "unconnected-(U6-IO22-Pad36)") (class "Default")
      (node (ref "U6") (pin "36") (pinfunction "IO22_36") (pintype "passive"))
    )
    (net (code "79") (name "unconnected-(U6-IO23-Pad37)") (class "Default")
      (node (ref "U6") (pin "37") (pinfunction "IO23_37") (pintype "passive"))
    )
    (net (code "80") (name "unconnected-(U6-IO25-Pad10)") (class "Default")
      (node (ref "U6") (pin "10") (pinfunction "IO25_10") (pintype "passive"))
    )
    (net (code "81") (name "unconnected-(U6-IO26-Pad11)") (class "Default")
      (node (ref "U6") (pin "11") (pinfunction "IO26_11") (pintype "passive"))
    )
    (net (code "82") (name "unconnected-(U6-IO27-Pad12)") (class "Default")
      (node (ref "U6") (pin "12") (pinfunction "IO27_12") (pintype "passive"))
    )
    (net (code "83") (name "unconnected-(U6-IO32-Pad8)") (class "Default")
      (node (ref "U6") (pin "8") (pinfunction "IO32_8") (pintype "passive"))
    )
    (net (code "84") (name "unconnected-(U6-IO33-Pad9)") (class "Default")
      (node (ref "U6") (pin "9") (pinfunction "IO33_9") (pintype "passive"))
    )
    (net (code "85") (name "unconnected-(U6-IO34-Pad6)") (class "Default")
      (node (ref "U6") (pin "6") (pinfunction "IO34_6") (pintype "passive"))
    )
    (net (code "86") (name "unconnected-(U6-IO35-Pad7)") (class "Default")
      (node (ref "U6") (pin "7") (pinfunction "IO35_7") (pintype "passive"))
    )
    (net (code "87") (name "unconnected-(U6-NC-Pad32)") (class "Default")
      (node (ref "U6") (pin "32") (pinfunction "NC_32") (pintype "passive"))
    )
    (net (code "88") (name "unconnected-(U6-SD0-Pad21)") (class "Default")
      (node (ref "U6") (pin "21") (pinfunction "SD0_21") (pintype "passive"))
    )
    (net (code "89") (name "unconnected-(U6-SD1-Pad22)") (class "Default")
      (node (ref "U6") (pin "22") (pinfunction "SD1_22") (pintype "passive"))
    )
    (net (code "90") (name "unconnected-(U6-SD2-Pad17)") (class "Default")
      (node (ref "U6") (pin "17") (pinfunction "SD2_17") (pintype "passive"))
    )
    (net (code "91") (name "unconnected-(U6-SD3-Pad18)") (class "Default")
      (node (ref "U6") (pin "18") (pinfunction "SD3_18") (pintype "passive"))
    )
    (net (code "92") (name "unconnected-(U6-SENSOR_VN-Pad5)") (class "Default")
      (node (ref "U6") (pin "5") (pinfunction "SENSOR_VN_5") (pintype "passive"))
    )
    (net (code "93") (name "unconnected-(U6-SENSOR_VP-Pad4)") (class "Default")
      (node (ref "U6") (pin "4") (pinfunction "SENSOR_VP_4") (pintype "passive"))
    )
    (net (code "94") (name "unconnected-(U7-FT{slash}OUT-Pad7)") (class "Default")
      (node (ref "U7") (pin "7") (pinfunction "FT/OUT_7") (pintype "passive"))
    )
  )
)
